# PROB_S7CAS_MOTDRIVER.net
KiCad netlist of a schematic drawn in Altium Designer
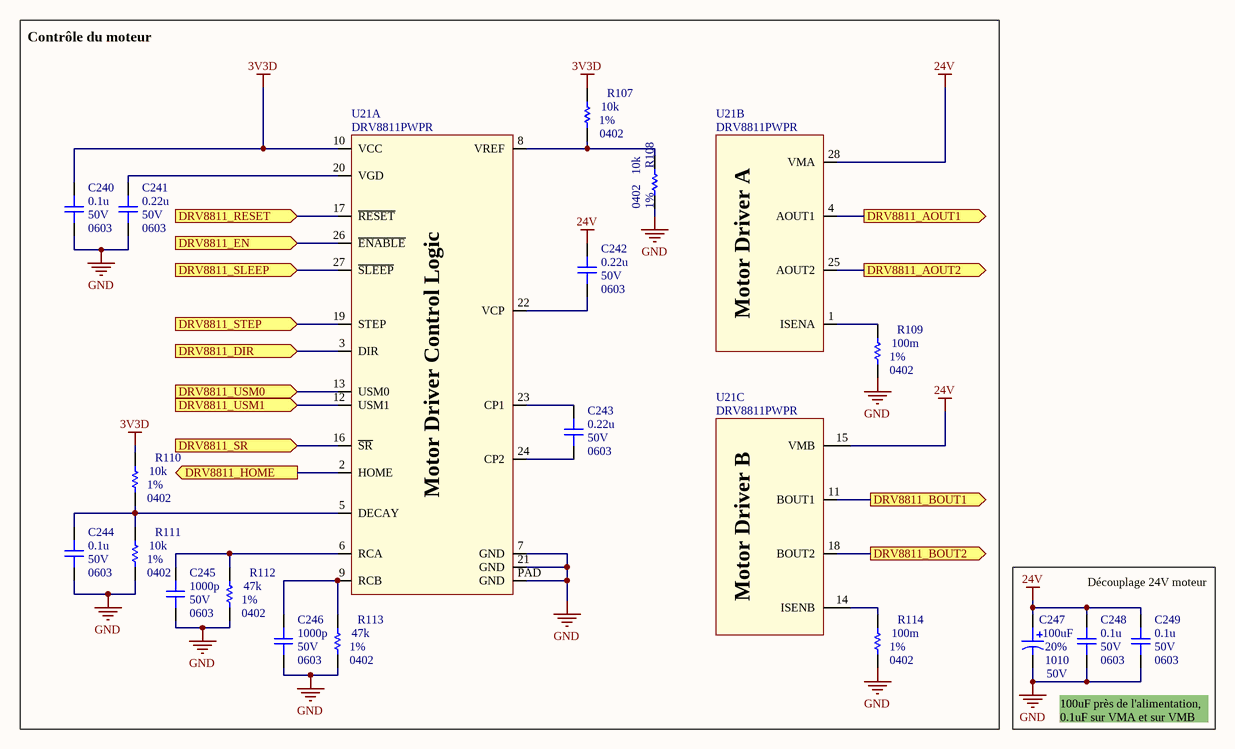
[diagram p0: PROB_S7CAS_MOTDRIVER.SchDoc]

(export (version "E")
  (design (tool "Eeschema 10.0.6"))
  (components
    (comp (ref "C240")
      (value "0.1u")
      (footprint "CAP_0603")
      (description "CAP - 0603")
      (fields
        (field (name "VOLTAGE") "50V")
        (field (name "PACKAGE") "0603")
        (field (name "CREATEDBY") "Jonathan Bouchard")
      )
      (libsource (lib "S7CAS_LIB2021") (part "CAP - 0603"))
    )
    (comp (ref "C241")
      (value "0.22u")
      (footprint "CAP_0603")
      (description "CAP - 0603")
      (fields
        (field (name "VOLTAGE") "50V")
        (field (name "PACKAGE") "0603")
        (field (name "CREATEDBY") "Jonathan Bouchard")
      )
      (libsource (lib "S7CAS_LIB2021") (part "CAP - 0603"))
    )
    (comp (ref "C242")
      (value "0.22u")
      (footprint "CAP_0603")
      (description "CAP - 0603")
      (fields
        (field (name "VOLTAGE") "50V")
        (field (name "PACKAGE") "0603")
        (field (name "CREATEDBY") "Jonathan Bouchard")
      )
      (libsource (lib "S7CAS_LIB2021") (part "CAP - 0603"))
    )
    (comp (ref "C243")
      (value "0.22u")
      (footprint "CAP_0603")
      (description "CAP - 0603")
      (fields
        (field (name "VOLTAGE") "50V")
        (field (name "PACKAGE") "0603")
        (field (name "CREATEDBY") "Jonathan Bouchard")
      )
      (libsource (lib "S7CAS_LIB2021") (part "CAP - 0603"))
    )
    (comp (ref "C244")
      (value "0.1u")
      (footprint "CAP_0603")
      (description "CAP - 0603")
      (fields
        (field (name "VOLTAGE") "50V")
        (field (name "PACKAGE") "0603")
        (field (name "CREATEDBY") "Jonathan Bouchard")
      )
      (libsource (lib "S7CAS_LIB2021") (part "CAP - 0603"))
    )
    (comp (ref "C245")
      (value "1000p")
      (footprint "CAP_0603")
      (description "CAP - 0603")
      (fields
        (field (name "VOLTAGE") "50V")
        (field (name "PACKAGE") "0603")
        (field (name "CREATEDBY") "Jonathan Bouchard")
      )
      (libsource (lib "S7CAS_LIB2021") (part "CAP - 0603"))
    )
    (comp (ref "C246")
      (value "1000p")
      (footprint "CAP_0603")
      (description "CAP - 0603")
      (fields
        (field (name "VOLTAGE") "50V")
        (field (name "PACKAGE") "0603")
        (field (name "CREATEDBY") "Jonathan Bouchard")
      )
      (libsource (lib "S7CAS_LIB2021") (part "CAP - 0603"))
    )
    (comp (ref "C247")
      (value "100uF")
      (footprint "CAP_ALU_1010_vishay")
      (description "CAP - ALU 100uF 20% 50V - 1010")
      (fields
        (field (name "MFG") "Vishay Dale")
        (field (name "MFG PART NUMBER") "MAL215099101E3")
        (field (name "VOLTAGE") "50V")
        (field (name "PACKAGE") "1010")
        (field (name "PRECISION") "20%")
        (field (name "CREATEDBY") "Jonathan Bouchard")
      )
      (libsource (lib "S7CAS_LIB2021") (part "CAP_ALU_MAL215099101E3"))
    )
    (comp (ref "C248")
      (value "0.1u")
      (footprint "CAP_0603")
      (description "CAP - 0603")
      (fields
        (field (name "VOLTAGE") "50V")
        (field (name "PACKAGE") "0603")
        (field (name "CREATEDBY") "Jonathan Bouchard")
      )
      (libsource (lib "S7CAS_LIB2021") (part "CAP - 0603"))
    )
    (comp (ref "C249")
      (value "0.1u")
      (footprint "CAP_0603")
      (description "CAP - 0603")
      (fields
        (field (name "VOLTAGE") "50V")
        (field (name "PACKAGE") "0603")
        (field (name "CREATEDBY") "Jonathan Bouchard")
      )
      (libsource (lib "S7CAS_LIB2021") (part "CAP - 0603"))
    )
    (comp (ref "R107")
      (value "10k")
      (footprint "RES_0402")
      (description "RES - 0402")
      (fields
        (field (name "VOLTAGE") "50V")
        (field (name "POWER") "1/16W")
        (field (name "PACKAGE") "0402")
        (field (name "PRECISION") "1%")
        (field (name "CREATEDBY") "Jonathan Bouchard")
      )
      (libsource (lib "S7CAS_LIB2021") (part "RES - 0402"))
    )
    (comp (ref "R108")
      (value "10k")
      (footprint "RES_0402")
      (description "RES - 0402")
      (fields
        (field (name "VOLTAGE") "50V")
        (field (name "POWER") "1/16W")
        (field (name "PACKAGE") "0402")
        (field (name "PRECISION") "1%")
        (field (name "CREATEDBY") "Jonathan Bouchard")
      )
      (libsource (lib "S7CAS_LIB2021") (part "RES - 0402"))
    )
    (comp (ref "R109")
      (value "100m")
      (footprint "RES_0402")
      (description "RES - 0402")
      (fields
        (field (name "VOLTAGE") "50V")
        (field (name "POWER") "1/16W")
        (field (name "PACKAGE") "0402")
        (field (name "PRECISION") "1%")
        (field (name "CREATEDBY") "Jonathan Bouchard")
      )
      (libsource (lib "S7CAS_LIB2021") (part "RES - 0402"))
    )
    (comp (ref "R110")
      (value "10k")
      (footprint "RES_0402")
      (description "RES - 0402")
      (fields
        (field (name "VOLTAGE") "50V")
        (field (name "POWER") "1/16W")
        (field (name "PACKAGE") "0402")
        (field (name "PRECISION") "1%")
        (field (name "CREATEDBY") "Jonathan Bouchard")
      )
      (libsource (lib "S7CAS_LIB2021") (part "RES - 0402"))
    )
    (comp (ref "R111")
      (value "10k")
      (footprint "RES_0402")
      (description "RES - 0402")
      (fields
        (field (name "VOLTAGE") "50V")
        (field (name "POWER") "1/16W")
        (field (name "PACKAGE") "0402")
        (field (name "PRECISION") "1%")
        (field (name "CREATEDBY") "Jonathan Bouchard")
      )
      (libsource (lib "S7CAS_LIB2021") (part "RES - 0402"))
    )
    (comp (ref "R112")
      (value "47k")
      (footprint "RES_0402")
      (description "RES - 0402")
      (fields
        (field (name "VOLTAGE") "50V")
        (field (name "POWER") "1/16W")
        (field (name "PACKAGE") "0402")
        (field (name "PRECISION") "1%")
        (field (name "CREATEDBY") "Jonathan Bouchard")
      )
      (libsource (lib "S7CAS_LIB2021") (part "RES - 0402"))
    )
    (comp (ref "R113")
      (value "47k")
      (footprint "RES_0402")
      (description "RES - 0402")
      (fields
        (field (name "VOLTAGE") "50V")
        (field (name "POWER") "1/16W")
        (field (name "PACKAGE") "0402")
        (field (name "PRECISION") "1%")
        (field (name "CREATEDBY") "Jonathan Bouchard")
      )
      (libsource (lib "S7CAS_LIB2021") (part "RES - 0402"))
    )
    (comp (ref "R114")
      (value "100m")
      (footprint "RES_0402")
      (description "RES - 0402")
      (fields
        (field (name "VOLTAGE") "50V")
        (field (name "POWER") "1/16W")
        (field (name "PACKAGE") "0402")
        (field (name "PRECISION") "1%")
        (field (name "CREATEDBY") "Jonathan Bouchard")
      )
      (libsource (lib "S7CAS_LIB2021") (part "RES - 0402"))
    )
    (comp (ref "U21")
      (value "DRV8811PWPR")
      (footprint "POW_MOTOR_DRV8811PWPR")
      (description "POW - STEPPER MOTOR DRIVER - SOP-28")
      (fields
        (field (name "VOLTAGE") "3 V ~ 5.5 V / 8 V ~ 38 V")
        (field (name "MFG") "Texas Instrument")
        (field (name "CREATEDBY") "Jonathan Bouchard")
      )
      (libsource (lib "S7CAS_LIB2021") (part "POW_MOTOR_DRV8811PWPR"))
    )
  )
  (nets
    (net (code "1") (name "/DRV8811_AOUT1") (class "Default")
      (node (ref "U21") (pin "4") (pinfunction "AOUT1_4") (pintype "passive"))
    )
    (net (code "2") (name "/DRV8811_AOUT2") (class "Default")
      (node (ref "U21") (pin "25") (pinfunction "AOUT2_25") (pintype "passive"))
    )
    (net (code "3") (name "/DRV8811_BOUT1") (class "Default")
      (node (ref "U21") (pin "11") (pinfunction "BOUT1_11") (pintype "passive"))
    )
    (net (code "4") (name "/DRV8811_BOUT2") (class "Default")
      (node (ref "U21") (pin "18") (pinfunction "BOUT2_18") (pintype "passive"))
    )
    (net (code "5") (name "/DRV8811_DIR") (class "Default")
      (node (ref "U21") (pin "3") (pinfunction "DIR_3") (pintype "passive"))
    )
    (net (code "6") (name "/DRV8811_EN") (class "Default")
      (node (ref "U21") (pin "26") (pinfunction "~{ENABLE}_26") (pintype "passive"))
    )
    (net (code "7") (name "/DRV8811_HOME") (class "Default")
      (node (ref "U21") (pin "2") (pinfunction "HOME_2") (pintype "passive"))
    )
    (net (code "8") (name "/DRV8811_RESET") (class "Default")
      (node (ref "U21") (pin "17") (pinfunction "~{RESET}_17") (pintype "passive"))
    )
    (net (code "9") (name "/DRV8811_SLEEP") (class "Default")
      (node (ref "U21") (pin "27") (pinfunction "~{SLEEP}_27") (pintype "passive"))
    )
    (net (code "10") (name "/DRV8811_SR") (class "Default")
      (node (ref "U21") (pin "16") (pinfunction "~{SR}_16") (pintype "passive"))
    )
    (net (code "11") (name "/DRV8811_STEP") (class "Default")
      (node (ref "U21") (pin "19") (pinfunction "STEP_19") (pintype "passive"))
    )
    (net (code "12") (name "/DRV8811_USM0") (class "Default")
      (node (ref "U21") (pin "13") (pinfunction "USM0_13") (pintype "passive"))
    )
    (net (code "13") (name "/DRV8811_USM1") (class "Default")
      (node (ref "U21") (pin "12") (pinfunction "USM1_12") (pintype "passive"))
    )
    (net (code "14") (name "3V3D") (class "Default")
      (node (ref "C240") (pin "2") (pinfunction "2_2") (pintype "passive"))
      (node (ref "R107") (pin "2") (pinfunction "2_2") (pintype "passive"))
      (node (ref "R110") (pin "2") (pinfunction "2_2") (pintype "passive"))
      (node (ref "U21") (pin "10") (pinfunction "VCC_10") (pintype "passive"))
    )
    (net (code "15") (name "24V") (class "Default")
      (node (ref "C242") (pin "2") (pinfunction "2_2") (pintype "passive"))
      (node (ref "C247") (pin "1") (pinfunction "1_1") (pintype "passive"))
      (node (ref "C248") (pin "2") (pinfunction "2_2") (pintype "passive"))
      (node (ref "C249") (pin "2") (pinfunction "2_2") (pintype "passive"))
      (node (ref "U21") (pin "15") (pinfunction "VMB_15") (pintype "passive"))
      (node (ref "U21") (pin "28") (pinfunction "VMA_28") (pintype "passive"))
    )
    (net (code "16") (name "GND") (class "Default")
      (node (ref "C240") (pin "1") (pinfunction "1_1") (pintype "passive"))
      (node (ref "C241") (pin "1") (pinfunction "1_1") (pintype "passive"))
      (node (ref "C244") (pin "1") (pinfunction "1_1") (pintype "passive"))
      (node (ref "C245") (pin "1") (pinfunction "1_1") (pintype "passive"))
      (node (ref "C246") (pin "1") (pinfunction "1_1") (pintype "passive"))
      (node (ref "C247") (pin "2") (pinfunction "2_2") (pintype "passive"))
      (node (ref "C248") (pin "1") (pinfunction "1_1") (pintype "passive"))
      (node (ref "C249") (pin "1") (pinfunction "1_1") (pintype "passive"))
      (node (ref "R108") (pin "2") (pinfunction "2_2") (pintype "passive"))
      (node (ref "R109") (pin "1") (pinfunction "1_1") (pintype "passive"))
      (node (ref "R111") (pin "1") (pinfunction "1_1") (pintype "passive"))
      (node (ref "R112") (pin "1") (pinfunction "1_1") (pintype "passive"))
      (node (ref "R113") (pin "1") (pinfunction "1_1") (pintype "passive"))
      (node (ref "R114") (pin "1") (pinfunction "1_1") (pintype "passive"))
      (node (ref "U21") (pin "21") (pinfunction "GND_21") (pintype "passive"))
      (node (ref "U21") (pin "7") (pinfunction "GND_7") (pintype "passive"))
      (node (ref "U21") (pin "PAD") (pinfunction "GND_PAD") (pintype "passive"))
    )
    (net (code "17") (name "Net-(U21A-CP1)") (class "Default")
      (node (ref "C243") (pin "2") (pinfunction "2_2") (pintype "passive"))
      (node (ref "U21") (pin "23") (pinfunction "CP1_23") (pintype "passive"))
    )
    (net (code "18") (name "Net-(U21A-CP2)") (class "Default")
      (node (ref "C243") (pin "1") (pinfunction "1_1") (pintype "passive"))
      (node (ref "U21") (pin "24") (pinfunction "CP2_24") (pintype "passive"))
    )
    (net (code "19") (name "Net-(U21A-DECAY)") (class "Default")
      (node (ref "C244") (pin "2") (pinfunction "2_2") (pintype "passive"))
      (node (ref "R110") (pin "1") (pinfunction "1_1") (pintype "passive"))
      (node (ref "R111") (pin "2") (pinfunction "2_2") (pintype "passive"))
      (node (ref "U21") (pin "5") (pinfunction "DECAY_5") (pintype "passive"))
    )
    (net (code "20") (name "Net-(U21A-RCA)") (class "Default")
      (node (ref "C245") (pin "2") (pinfunction "2_2") (pintype "passive"))
      (node (ref "R112") (pin "2") (pinfunction "2_2") (pintype "passive"))
      (node (ref "U21") (pin "6") (pinfunction "RCA_6") (pintype "passive"))
    )
    (net (code "21") (name "Net-(U21A-RCB)") (class "Default")
      (node (ref "C246") (pin "2") (pinfunction "2_2") (pintype "passive"))
      (node (ref "R113") (pin "2") (pinfunction "2_2") (pintype "passive"))
      (node (ref "U21") (pin "9") (pinfunction "RCB_9") (pintype "passive"))
    )
    (net (code "22") (name "Net-(U21A-VCP)") (class "Default")
      (node (ref "C242") (pin "1") (pinfunction "1_1") (pintype "passive"))
      (node (ref "U21") (pin "22") (pinfunction "VCP_22") (pintype "passive"))
    )
    (net (code "23") (name "Net-(U21A-VGD)") (class "Default")
      (node (ref "C241") (pin "2") (pinfunction "2_2") (pintype "passive"))
      (node (ref "U21") (pin "20") (pinfunction "VGD_20") (pintype "passive"))
    )
    (net (code "24") (name "Net-(U21A-VREF)") (class "Default")
      (node (ref "R107") (pin "1") (pinfunction "1_1") (pintype "passive"))
      (node (ref "R108") (pin "1") (pinfunction "1_1") (pintype "passive"))
      (node (ref "U21") (pin "8") (pinfunction "VREF_8") (pintype "passive"))
    )
    (net (code "25") (name "Net-(U21B-ISENA)") (class "Default")
      (node (ref "R109") (pin "2") (pinfunction "2_2") (pintype "passive"))
      (node (ref "U21") (pin "1") (pinfunction "ISENA_1") (pintype "passive"))
    )
    (net (code "26") (name "Net-(U21C-ISENB)") (class "Default")
      (node (ref "R114") (pin "2") (pinfunction "2_2") (pintype "passive"))
      (node (ref "U21") (pin "14") (pinfunction "ISENB_14") (pintype "passive"))
    )
  )
)
